# lilla.net
KiCad netlist of a schematic drawn in EAGLE
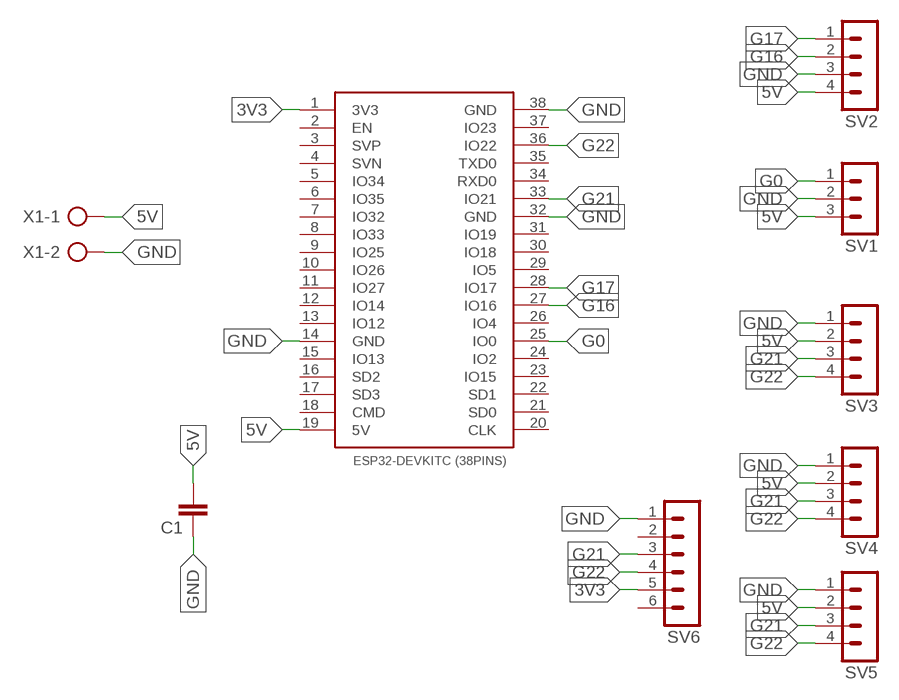
[diagram p0: schematic, sheet 1]

(export (version "E")
  (design (tool "Eeschema 10.0.6"))
  (components
    (comp (ref "C1")
      (value "C-EU050-024X044")
      (footprint "eagle-import:C050-024X044")
      (libsource (lib "eagle-import") (part "C-EU050-024X044"))
    )
    (comp (ref "ESP32-DEVKITC(38PINS)2")
      (value "ESP32DEVKITC_38PINS")
      (footprint "eagle-import:ESP32-DEVKITC")
      (libsource (lib "eagle-import") (part "ESP32DEVKITC_38PINS"))
    )
    (comp (ref "SV1")
      (value "MA03-1")
      (footprint "eagle-import:MA03-1")
      (libsource (lib "eagle-import") (part "MA03-1"))
    )
    (comp (ref "SV2")
      (value "MA04-1")
      (footprint "eagle-import:MA04-1")
      (libsource (lib "eagle-import") (part "MA04-1"))
    )
    (comp (ref "SV3")
      (value "MA04-1")
      (footprint "eagle-import:MA04-1")
      (libsource (lib "eagle-import") (part "MA04-1"))
    )
    (comp (ref "SV4")
      (value "MA04-1")
      (footprint "eagle-import:MA04-1")
      (libsource (lib "eagle-import") (part "MA04-1"))
    )
    (comp (ref "SV5")
      (value "MA04-1")
      (footprint "eagle-import:MA04-1")
      (libsource (lib "eagle-import") (part "MA04-1"))
    )
    (comp (ref "SV6")
      (value "MA06-1")
      (footprint "eagle-import:MA06-1")
      (libsource (lib "eagle-import") (part "MA06-1"))
    )
    (comp (ref "X1")
      (value "AK300/2")
      (footprint "eagle-import:AK300_2")
      (libsource (lib "eagle-import") (part "AK300/2"))
    )
  )
  (nets
    (net (code "1") (name "3V3") (class "Default")
      (node (ref "ESP32-DEVKITC(38PINS)2") (pin "1") (pinfunction "3V3_1") (pintype "bidirectional"))
      (node (ref "SV6") (pin "5") (pinfunction "5_5") (pintype "passive"))
    )
    (net (code "2") (name "5V") (class "Default")
      (node (ref "C1") (pin "2") (pinfunction "2_2") (pintype "passive"))
      (node (ref "ESP32-DEVKITC(38PINS)2") (pin "19") (pinfunction "5V_19") (pintype "bidirectional"))
      (node (ref "SV1") (pin "3") (pinfunction "3_3") (pintype "passive"))
      (node (ref "SV2") (pin "4") (pinfunction "4_4") (pintype "passive"))
      (node (ref "SV3") (pin "2") (pinfunction "2_2") (pintype "passive"))
      (node (ref "SV4") (pin "2") (pinfunction "2_2") (pintype "passive"))
      (node (ref "SV5") (pin "2") (pinfunction "2_2") (pintype "passive"))
      (node (ref "X1") (pin "1") (pinfunction "KL_1") (pintype "passive"))
    )
    (net (code "3") (name "G0") (class "Default")
      (node (ref "ESP32-DEVKITC(38PINS)2") (pin "25") (pinfunction "IO0_25") (pintype "bidirectional"))
      (node (ref "SV1") (pin "1") (pinfunction "1_1") (pintype "passive"))
    )
    (net (code "4") (name "G16") (class "Default")
      (node (ref "ESP32-DEVKITC(38PINS)2") (pin "27") (pinfunction "IO16_27") (pintype "bidirectional"))
      (node (ref "SV2") (pin "2") (pinfunction "2_2") (pintype "passive"))
    )
    (net (code "5") (name "G17") (class "Default")
      (node (ref "ESP32-DEVKITC(38PINS)2") (pin "28") (pinfunction "IO17_28") (pintype "bidirectional"))
      (node (ref "SV2") (pin "1") (pinfunction "1_1") (pintype "passive"))
    )
    (net (code "6") (name "G21") (class "Default")
      (node (ref "ESP32-DEVKITC(38PINS)2") (pin "33") (pinfunction "IO21_33") (pintype "bidirectional"))
      (node (ref "SV3") (pin "3") (pinfunction "3_3") (pintype "passive"))
      (node (ref "SV4") (pin "3") (pinfunction "3_3") (pintype "passive"))
      (node (ref "SV5") (pin "3") (pinfunction "3_3") (pintype "passive"))
      (node (ref "SV6") (pin "3") (pinfunction "3_3") (pintype "passive"))
    )
    (net (code "7") (name "G22") (class "Default")
      (node (ref "ESP32-DEVKITC(38PINS)2") (pin "36") (pinfunction "IO22_36") (pintype "bidirectional"))
      (node (ref "SV3") (pin "4") (pinfunction "4_4") (pintype "passive"))
      (node (ref "SV4") (pin "4") (pinfunction "4_4") (pintype "passive"))
      (node (ref "SV5") (pin "4") (pinfunction "4_4") (pintype "passive"))
      (node (ref "SV6") (pin "4") (pinfunction "4_4") (pintype "passive"))
    )
    (net (code "8") (name "GND") (class "Default")
      (node (ref "C1") (pin "1") (pinfunction "1_1") (pintype "passive"))
      (node (ref "ESP32-DEVKITC(38PINS)2") (pin "14") (pinfunction "GND_14") (pintype "bidirectional"))
      (node (ref "ESP32-DEVKITC(38PINS)2") (pin "32") (pinfunction "GND_32") (pintype "bidirectional"))
      (node (ref "ESP32-DEVKITC(38PINS)2") (pin "38") (pinfunction "GND_38") (pintype "bidirectional"))
      (node (ref "SV1") (pin "2") (pinfunction "2_2") (pintype "passive"))
      (node (ref "SV2") (pin "3") (pinfunction "3_3") (pintype "passive"))
      (node (ref "SV3") (pin "1") (pinfunction "1_1") (pintype "passive"))
      (node (ref "SV4") (pin "1") (pinfunction "1_1") (pintype "passive"))
      (node (ref "SV5") (pin "1") (pinfunction "1_1") (pintype "passive"))
      (node (ref "SV6") (pin "1") (pinfunction "1_1") (pintype "passive"))
      (node (ref "X1") (pin "2") (pinfunction "KL_2") (pintype "passive"))
    )
    (net (code "9") (name "unconnected-(ESP32-DEVKITC(38PINS)2-CLK-Pad20)") (class "Default")
      (node (ref "ESP32-DEVKITC(38PINS)2") (pin "20") (pinfunction "CLK_20") (pintype "bidirectional"))
    )
    (net (code "10") (name "unconnected-(ESP32-DEVKITC(38PINS)2-CMD-Pad18)") (class "Default")
      (node (ref "ESP32-DEVKITC(38PINS)2") (pin "18") (pinfunction "CMD_18") (pintype "bidirectional"))
    )
    (net (code "11") (name "unconnected-(ESP32-DEVKITC(38PINS)2-EN-Pad2)") (class "Default")
      (node (ref "ESP32-DEVKITC(38PINS)2") (pin "2") (pinfunction "EN_2") (pintype "bidirectional"))
    )
    (net (code "12") (name "unconnected-(ESP32-DEVKITC(38PINS)2-IO2-Pad24)") (class "Default")
      (node (ref "ESP32-DEVKITC(38PINS)2") (pin "24") (pinfunction "IO2_24") (pintype "bidirectional"))
    )
    (net (code "13") (name "unconnected-(ESP32-DEVKITC(38PINS)2-IO4-Pad26)") (class "Default")
      (node (ref "ESP32-DEVKITC(38PINS)2") (pin "26") (pinfunction "IO4_26") (pintype "bidirectional"))
    )
    (net (code "14") (name "unconnected-(ESP32-DEVKITC(38PINS)2-IO5-Pad29)") (class "Default")
      (node (ref "ESP32-DEVKITC(38PINS)2") (pin "29") (pinfunction "IO5_29") (pintype "bidirectional"))
    )
    (net (code "15") (name "unconnected-(ESP32-DEVKITC(38PINS)2-IO12-Pad13)") (class "Default")
      (node (ref "ESP32-DEVKITC(38PINS)2") (pin "13") (pinfunction "IO12_13") (pintype "bidirectional"))
    )
    (net (code "16") (name "unconnected-(ESP32-DEVKITC(38PINS)2-IO13-Pad15)") (class "Default")
      (node (ref "ESP32-DEVKITC(38PINS)2") (pin "15") (pinfunction "IO13_15") (pintype "bidirectional"))
    )
    (net (code "17") (name "unconnected-(ESP32-DEVKITC(38PINS)2-IO14-Pad12)") (class "Default")
      (node (ref "ESP32-DEVKITC(38PINS)2") (pin "12") (pinfunction "IO14_12") (pintype "bidirectional"))
    )
    (net (code "18") (name "unconnected-(ESP32-DEVKITC(38PINS)2-IO15-Pad23)") (class "Default")
      (node (ref "ESP32-DEVKITC(38PINS)2") (pin "23") (pinfunction "IO15_23") (pintype "bidirectional"))
    )
    (net (code "19") (name "unconnected-(ESP32-DEVKITC(38PINS)2-IO18-Pad30)") (class "Default")
      (node (ref "ESP32-DEVKITC(38PINS)2") (pin "30") (pinfunction "IO18_30") (pintype "bidirectional"))
    )
    (net (code "20") (name "unconnected-(ESP32-DEVKITC(38PINS)2-IO19-Pad31)") (class "Default")
      (node (ref "ESP32-DEVKITC(38PINS)2") (pin "31") (pinfunction "IO19_31") (pintype "bidirectional"))
    )
    (net (code "21") (name "unconnected-(ESP32-DEVKITC(38PINS)2-IO23-Pad37)") (class "Default")
      (node (ref "ESP32-DEVKITC(38PINS)2") (pin "37") (pinfunction "IO23_37") (pintype "bidirectional"))
    )
    (net (code "22") (name "unconnected-(ESP32-DEVKITC(38PINS)2-IO25-Pad9)") (class "Default")
      (node (ref "ESP32-DEVKITC(38PINS)2") (pin "9") (pinfunction "IO25_9") (pintype "bidirectional"))
    )
    (net (code "23") (name "unconnected-(ESP32-DEVKITC(38PINS)2-IO26-Pad10)") (class "Default")
      (node (ref "ESP32-DEVKITC(38PINS)2") (pin "10") (pinfunction "IO26_10") (pintype "bidirectional"))
    )
    (net (code "24") (name "unconnected-(ESP32-DEVKITC(38PINS)2-IO27-Pad11)") (class "Default")
      (node (ref "ESP32-DEVKITC(38PINS)2") (pin "11") (pinfunction "IO27_11") (pintype "bidirectional"))
    )
    (net (code "25") (name "unconnected-(ESP32-DEVKITC(38PINS)2-IO32-Pad7)") (class "Default")
      (node (ref "ESP32-DEVKITC(38PINS)2") (pin "7") (pinfunction "IO32_7") (pintype "bidirectional"))
    )
    (net (code "26") (name "unconnected-(ESP32-DEVKITC(38PINS)2-IO33-Pad8)") (class "Default")
      (node (ref "ESP32-DEVKITC(38PINS)2") (pin "8") (pinfunction "IO33_8") (pintype "bidirectional"))
    )
    (net (code "27") (name "unconnected-(ESP32-DEVKITC(38PINS)2-IO34-Pad5)") (class "Default")
      (node (ref "ESP32-DEVKITC(38PINS)2") (pin "5") (pinfunction "IO34_5") (pintype "bidirectional"))
    )
    (net (code "28") (name "unconnected-(ESP32-DEVKITC(38PINS)2-IO35-Pad6)") (class "Default")
      (node (ref "ESP32-DEVKITC(38PINS)2") (pin "6") (pinfunction "IO35_6") (pintype "bidirectional"))
    )
    (net (code "29") (name "unconnected-(ESP32-DEVKITC(38PINS)2-RXD0-Pad34)") (class "Default")
      (node (ref "ESP32-DEVKITC(38PINS)2") (pin "34") (pinfunction "RXD0_34") (pintype "bidirectional"))
    )
    (net (code "30") (name "unconnected-(ESP32-DEVKITC(38PINS)2-SD0-Pad21)") (class "Default")
      (node (ref "ESP32-DEVKITC(38PINS)2") (pin "21") (pinfunction "SD0_21") (pintype "bidirectional"))
    )
    (net (code "31") (name "unconnected-(ESP32-DEVKITC(38PINS)2-SD1-Pad22)") (class "Default")
      (node (ref "ESP32-DEVKITC(38PINS)2") (pin "22") (pinfunction "SD1_22") (pintype "bidirectional"))
    )
    (net (code "32") (name "unconnected-(ESP32-DEVKITC(38PINS)2-SD2-Pad16)") (class "Default")
      (node (ref "ESP32-DEVKITC(38PINS)2") (pin "16") (pinfunction "SD2_16") (pintype "bidirectional"))
    )
    (net (code "33") (name "unconnected-(ESP32-DEVKITC(38PINS)2-SD3-Pad17)") (class "Default")
      (node (ref "ESP32-DEVKITC(38PINS)2") (pin "17") (pinfunction "SD3_17") (pintype "bidirectional"))
    )
    (net (code "34") (name "unconnected-(ESP32-DEVKITC(38PINS)2-SVN-Pad4)") (class "Default")
      (node (ref "ESP32-DEVKITC(38PINS)2") (pin "4") (pinfunction "SVN_4") (pintype "bidirectional"))
    )
    (net (code "35") (name "unconnected-(ESP32-DEVKITC(38PINS)2-SVP-Pad3)") (class "Default")
      (node (ref "ESP32-DEVKITC(38PINS)2") (pin "3") (pinfunction "SVP_3") (pintype "bidirectional"))
    )
    (net (code "36") (name "unconnected-(ESP32-DEVKITC(38PINS)2-TXD0-Pad35)") (class "Default")
      (node (ref "ESP32-DEVKITC(38PINS)2") (pin "35") (pinfunction "TXD0_35") (pintype "bidirectional"))
    )
    (net (code "37") (name "unconnected-(SV6-Pad2)") (class "Default")
      (node (ref "SV6") (pin "2") (pinfunction "2_2") (pintype "passive"))
    )
    (net (code "38") (name "unconnected-(SV6-Pad6)") (class "Default")
      (node (ref "SV6") (pin "6") (pinfunction "6_6") (pintype "passive"))
    )
  )
)
